# driver.net
KiCad netlist of a schematic drawn in Altium Designer
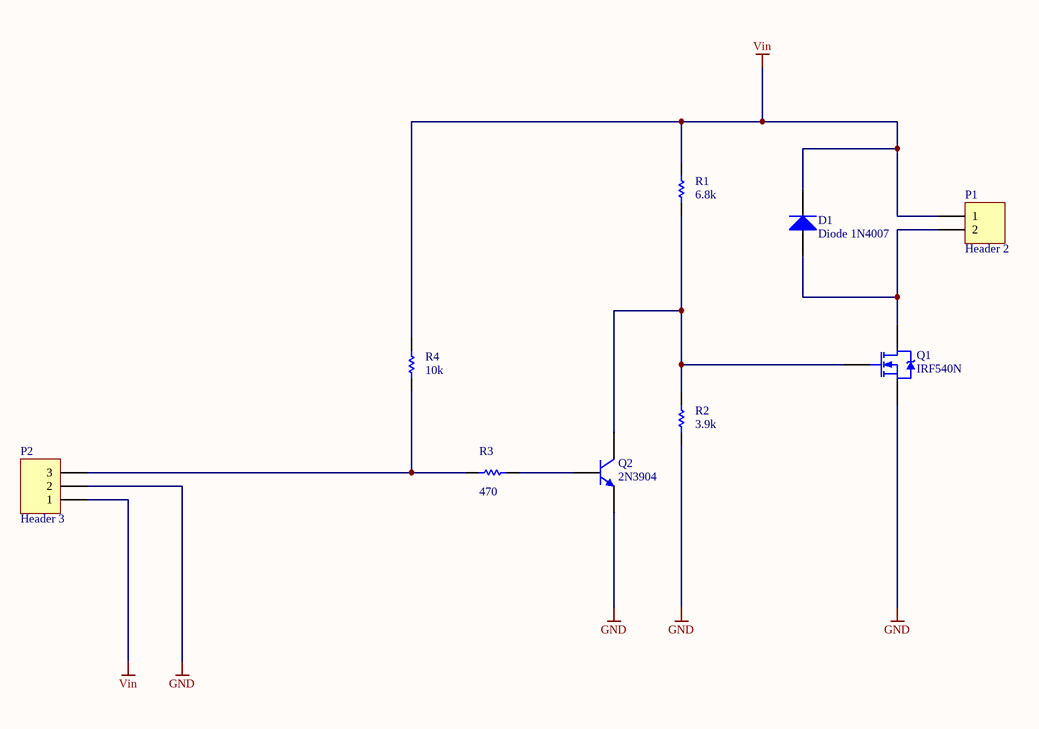
[diagram p0: driver.SchDoc]

(export (version "E")
  (design (tool "Eeschema 10.0.6"))
  (components
    (comp (ref "D1")
      (value "Diode 1N4007")
      (footprint "DO-41")
      (description "1 Amp General Purpose Rectifier")
      (fields (field (name "PUBLISHER") "Altium Limited"))
      (libsource (lib "Miscellaneous Devices") (part "Diode 1N4007"))
    )
    (comp (ref "P1")
      (value "Header 2")
      (footprint "HDR1X2")
      (description "Header, 2-Pin")
      (fields (field (name "PUBLISHER") "Altium Limited"))
      (libsource (lib "Miscellaneous Connectors") (part "Header 2"))
    )
    (comp (ref "P2")
      (value "Header 3")
      (footprint "HDR1X3")
      (description "Header, 3-Pin")
      (fields (field (name "PUBLISHER") "Altium Limited"))
      (libsource (lib "Miscellaneous Connectors") (part "Header 3"))
    )
    (comp (ref "Q1")
      (value "IRF540N")
      (footprint "TO-220AB")
      (description "HEXFET Power MOSFET")
      (fields (field (name "PUBLISHER") "Altium Limited"))
      (libsource (lib "IR Discrete MOSFET - Power") (part "IRF540N"))
    )
    (comp (ref "Q2")
      (value "2N3904")
      (footprint "TO-92A")
      (description "NPN General Purpose Amplifier")
      (fields (field (name "PUBLISHER") "Altium Limited"))
      (libsource (lib "Miscellaneous Devices") (part "2N3904"))
    )
    (comp (ref "R1")
      (value "6.8k")
      (footprint "AXIAL-0.3")
      (description "Resistor")
      (fields (field (name "Comment") "Res1") (field (name "PUBLISHER") "Altium Limited"))
      (libsource (lib "Miscellaneous Devices") (part "Res1"))
    )
    (comp (ref "R2")
      (value "3.9k")
      (footprint "AXIAL-0.3")
      (description "Resistor")
      (fields (field (name "Comment") "Res1") (field (name "PUBLISHER") "Altium Limited"))
      (libsource (lib "Miscellaneous Devices") (part "Res1"))
    )
    (comp (ref "R3")
      (value "470")
      (footprint "AXIAL-0.3")
      (description "Resistor")
      (fields (field (name "Comment") "Res1") (field (name "PUBLISHER") "Altium Limited"))
      (libsource (lib "Miscellaneous Devices") (part "Res1"))
    )
    (comp (ref "R4")
      (value "10k")
      (footprint "AXIAL-0.3")
      (description "Resistor")
      (fields (field (name "Comment") "Res1") (field (name "PUBLISHER") "Altium Limited"))
      (libsource (lib "Miscellaneous Devices") (part "Res1"))
    )
  )
  (nets
    (net (code "1") (name "GND") (class "Default")
      (node (ref "P2") (pin "2") (pinfunction "2_2") (pintype "passive"))
      (node (ref "Q1") (pin "3") (pinfunction "S_3") (pintype "passive"))
      (node (ref "Q2") (pin "1") (pinfunction "E_1") (pintype "passive"))
      (node (ref "R2") (pin "1") (pinfunction "1_1") (pintype "passive"))
    )
    (net (code "2") (name "Net-(D1-A)") (class "Default")
      (node (ref "D1") (pin "1") (pinfunction "A_1") (pintype "passive"))
      (node (ref "P1") (pin "2") (pinfunction "2_2") (pintype "passive"))
      (node (ref "Q1") (pin "2") (pinfunction "D_2") (pintype "passive"))
    )
    (net (code "3") (name "Net-(P2-Pad3)") (class "Default")
      (node (ref "P2") (pin "3") (pinfunction "3_3") (pintype "passive"))
      (node (ref "R3") (pin "2") (pinfunction "2_2") (pintype "passive"))
      (node (ref "R4") (pin "1") (pinfunction "1_1") (pintype "passive"))
    )
    (net (code "4") (name "Net-(Q1-G)") (class "Default")
      (node (ref "Q1") (pin "1") (pinfunction "G_1") (pintype "passive"))
      (node (ref "Q2") (pin "3") (pinfunction "C_3") (pintype "passive"))
      (node (ref "R1") (pin "1") (pinfunction "1_1") (pintype "passive"))
      (node (ref "R2") (pin "2") (pinfunction "2_2") (pintype "passive"))
    )
    (net (code "5") (name "Net-(Q2-B)") (class "Default")
      (node (ref "Q2") (pin "2") (pinfunction "B_2") (pintype "passive"))
      (node (ref "R3") (pin "1") (pinfunction "1_1") (pintype "passive"))
    )
    (net (code "6") (name "Vin") (class "Default")
      (node (ref "D1") (pin "2") (pinfunction "K_2") (pintype "passive"))
      (node (ref "P1") (pin "1") (pinfunction "1_1") (pintype "passive"))
      (node (ref "P2") (pin "1") (pinfunction "1_1") (pintype "passive"))
      (node (ref "R1") (pin "2") (pinfunction "2_2") (pintype "passive"))
      (node (ref "R4") (pin "2") (pinfunction "2_2") (pintype "passive"))
    )
  )
)
